# Cell.net
KiCad netlist of a schematic drawn in Altium Designer
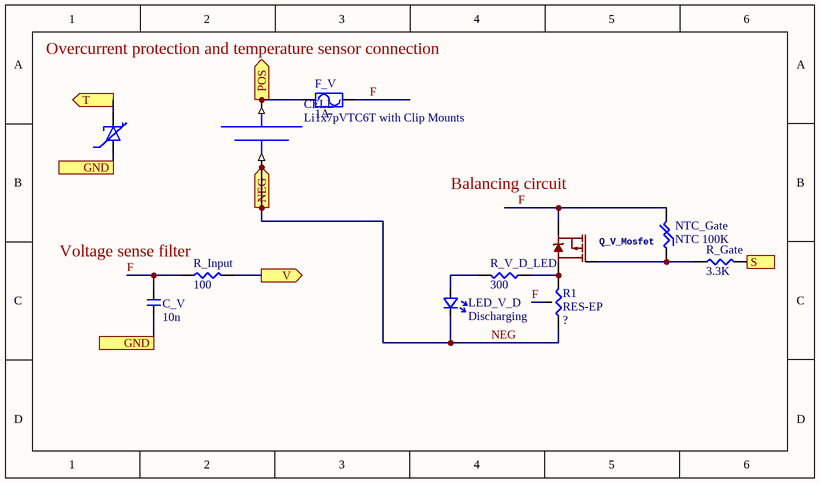
[diagram p0: Cell.SchDoc]

(export (version "E")
  (design (tool "Eeschema 10.0.6"))
  (components
    (comp (ref "CELL")
      (value "Li1x7pVTC6T with Clip Mounts")
      (footprint "Li1x7pVTC6T_Clips")
      (libsource (lib "LTC6811") (part "Li1x7pVTC6T_Clip"))
    )
    (comp (ref "C_V")
      (value "10n")
      (footprint "CAP-0603")
      (description "CAP-0603")
      (libsource (lib "altium-import") (part "root_1_CAP-0603_"))
    )
    (comp (ref "F_V")
      (value "1A")
      (footprint "2410SMD")
      (description "0679L")
      (libsource (lib "altium-import") (part "root_0_0679L_"))
    )
    (comp (ref "LED_V_D")
      (value "Discharging")
      (footprint "LED-0603")
      (description "LED-0603")
      (libsource (lib "altium-import") (part "root_3_LED-0603_"))
    )
    (comp (ref "NTC_Gate")
      (value "NTC 100K")
      (footprint "NTC-0603")
      (description "NTC-0603")
      (libsource (lib "altium-import") (part "root_1_NTC-0603_"))
    )
    (comp (ref "Q_V_Mosfet")
      (value "~")
      (footprint "TO252")
      (description "DMP10H400SK3-13")
      (libsource (lib "altium-import") (part "root_0_DMP10H400SK3-13_"))
    )
    (comp (ref "R1")
      (value "RES-EP")
      (footprint "RES-TO252")
      (description "RES SMD TO252")
      (fields (field (name "PART") "RES_TO252") (field (name "ALTIUM_VALUE") "?"))
      (libsource (lib "IFE") (part "RES-EP"))
    )
    (comp (ref "R_Gate")
      (value "3.3K")
      (footprint "RES-0603")
      (libsource (lib "altium-import") (part "root_0_RES-0603_"))
    )
    (comp (ref "R_Input")
      (value "100")
      (footprint "RES-0603")
      (libsource (lib "altium-import") (part "root_0_RES-0603_"))
    )
    (comp (ref "R_V_D_LED")
      (value "300")
      (footprint "RES-0603")
      (libsource (lib "altium-import") (part "root_2_RES-0603_"))
    )
  )
  (nets
    (net (code "1") (name "/F") (class "Default")
      (node (ref "C_V") (pin "2") (pinfunction "2_2") (pintype "passive"))
      (node (ref "F_V") (pin "1") (pinfunction "1_1") (pintype "passive"))
      (node (ref "NTC_Gate") (pin "2") (pinfunction "2_2") (pintype "passive"))
      (node (ref "Q_V_Mosfet") (pin "3") (pinfunction "S_3") (pintype "passive"))
      (node (ref "R1") (pin "3") (pinfunction "3_3") (pintype "passive"))
      (node (ref "R_Input") (pin "1") (pinfunction "1_1") (pintype "passive"))
    )
    (net (code "2") (name "/GND") (class "Default")
      (node (ref "CELL") (pin "T-") (pinfunction "T-_T-") (pintype "passive"))
      (node (ref "C_V") (pin "1") (pinfunction "1_1") (pintype "passive"))
    )
    (net (code "3") (name "/NEG") (class "Default")
      (node (ref "CELL") (pin "-") (pinfunction "-_-") (pintype "input"))
      (node (ref "CELL") (pin "-L") (pinfunction "-L_-L") (pintype "passive"))
      (node (ref "CELL") (pin "-O") (pinfunction "-O_-O") (pintype "passive"))
      (node (ref "CELL") (pin "-R") (pinfunction "-R_-R") (pintype "passive"))
      (node (ref "LED_V_D") (pin "K") (pinfunction "K_K") (pintype "passive"))
      (node (ref "R1") (pin "1") (pinfunction "1_1") (pintype "passive"))
    )
    (net (code "4") (name "/POS") (class "Default")
      (node (ref "CELL") (pin "+") (pinfunction "+_+") (pintype "output"))
      (node (ref "CELL") (pin "+L") (pinfunction "+L_+L") (pintype "passive"))
      (node (ref "CELL") (pin "+O") (pinfunction "+O_+O") (pintype "passive"))
      (node (ref "CELL") (pin "+R") (pinfunction "+R_+R") (pintype "passive"))
      (node (ref "F_V") (pin "2") (pinfunction "2_2") (pintype "passive"))
    )
    (net (code "5") (name "/S") (class "Default")
      (node (ref "R_Gate") (pin "2") (pinfunction "2_2") (pintype "passive"))
    )
    (net (code "6") (name "/T") (class "Default")
      (node (ref "CELL") (pin "T+") (pinfunction "T+_T+") (pintype "passive"))
    )
    (net (code "7") (name "/V") (class "Default")
      (node (ref "R_Input") (pin "2") (pinfunction "2_2") (pintype "passive"))
    )
    (net (code "8") (name "Net-(LED_V_D-PadA)") (class "Default")
      (node (ref "LED_V_D") (pin "A") (pinfunction "A_A") (pintype "passive"))
      (node (ref "R_V_D_LED") (pin "2") (pinfunction "2_2") (pintype "passive"))
    )
    (net (code "9") (name "Net-(Q_V_Mosfet-D)") (class "Default")
      (node (ref "Q_V_Mosfet") (pin "2") (pinfunction "D_2") (pintype "passive"))
      (node (ref "R1") (pin "2") (pinfunction "2_2") (pintype "passive"))
      (node (ref "R_V_D_LED") (pin "1") (pinfunction "1_1") (pintype "passive"))
    )
    (net (code "10") (name "Net-(Q_V_Mosfet-G)") (class "Default")
      (node (ref "NTC_Gate") (pin "1") (pinfunction "1_1") (pintype "passive"))
      (node (ref "Q_V_Mosfet") (pin "1") (pinfunction "G_1") (pintype "passive"))
      (node (ref "R_Gate") (pin "1") (pinfunction "1_1") (pintype "passive"))
    )
  )
)
